# rs232module.net
KiCad netlist of a schematic drawn in EAGLE
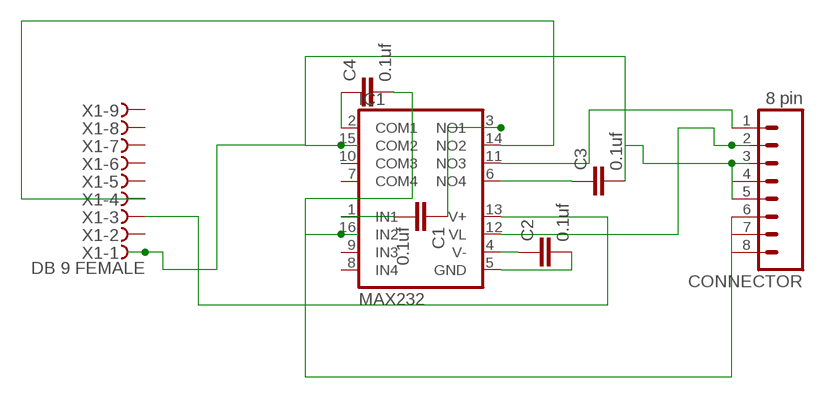
[diagram p0: schematic, sheet 1]

(export (version "E")
  (design (tool "Eeschema 10.0.6"))
  (components
    (comp (ref "C1")
      (value "0.1uf")
      (footprint "eagle-import:C2.5-3")
      (libsource (lib "eagle-import") (part "C2,5-3"))
    )
    (comp (ref "C2")
      (value "0.1uf")
      (footprint "eagle-import:C2.5-3")
      (libsource (lib "eagle-import") (part "C2,5-3"))
    )
    (comp (ref "C3")
      (value "0.1uf")
      (footprint "eagle-import:C2.5-3")
      (libsource (lib "eagle-import") (part "C2,5-3"))
    )
    (comp (ref "C4")
      (value "0.1uf")
      (footprint "eagle-import:C2.5-3")
      (libsource (lib "eagle-import") (part "C2,5-3"))
    )
    (comp (ref "CONNECTOR")
      (value "8 pin")
      (footprint "eagle-import:08P")
      (libsource (lib "eagle-import") (part "M08"))
    )
    (comp (ref "IC1")
      (value "MAX232")
      (footprint "eagle-import:DIL16")
      (fields (field (name "MPN") "MAX313EPE+"))
      (libsource (lib "eagle-import") (part "MAX313PEE"))
    )
    (comp (ref "X1")
      (value "DB 9 FEMALE")
      (footprint "eagle-import:H2M09ST")
      (libsource (lib "eagle-import") (part "D-SUB9-H2M09ST"))
    )
  )
  (nets
    (net (code "1") (name "Net-(IC1-COM1)") (class "Default")
      (node (ref "C4") (pin "1") (pinfunction "1_1") (pintype "passive"))
      (node (ref "IC1") (pin "2") (pinfunction "COM1_2") (pintype "passive"))
    )
    (net (code "2") (name "Net-(IC1-COM2)") (class "Default")
      (node (ref "C3") (pin "2") (pinfunction "2_2") (pintype "passive"))
      (node (ref "CONNECTOR") (pin "3") (pinfunction "3_3") (pintype "passive"))
      (node (ref "CONNECTOR") (pin "4") (pinfunction "4_4") (pintype "passive"))
      (node (ref "CONNECTOR") (pin "5") (pinfunction "5_5") (pintype "passive"))
      (node (ref "IC1") (pin "15") (pinfunction "COM2_15") (pintype "passive"))
      (node (ref "X1") (pin "1") (pinfunction "F_1") (pintype "passive"))
    )
    (net (code "3") (name "Net-(IC1-GND)") (class "Default")
      (node (ref "C2") (pin "2") (pinfunction "2_2") (pintype "passive"))
      (node (ref "IC1") (pin "5") (pinfunction "GND_5") (pintype "power_in"))
    )
    (net (code "4") (name "Net-(IC1-IN1)") (class "Default")
      (node (ref "C1") (pin "2") (pinfunction "2_2") (pintype "passive"))
      (node (ref "IC1") (pin "1") (pinfunction "IN1_1") (pintype "input"))
    )
    (net (code "5") (name "Net-(IC1-IN2)") (class "Default")
      (node (ref "C4") (pin "2") (pinfunction "2_2") (pintype "passive"))
      (node (ref "CONNECTOR") (pin "6") (pinfunction "6_6") (pintype "passive"))
      (node (ref "CONNECTOR") (pin "7") (pinfunction "7_7") (pintype "passive"))
      (node (ref "CONNECTOR") (pin "8") (pinfunction "8_8") (pintype "passive"))
      (node (ref "IC1") (pin "16") (pinfunction "IN2_16") (pintype "input"))
    )
    (net (code "6") (name "Net-(IC1-NO1)") (class "Default")
      (node (ref "C1") (pin "1") (pinfunction "1_1") (pintype "passive"))
      (node (ref "IC1") (pin "3") (pinfunction "NO1_3") (pintype "passive"))
    )
    (net (code "7") (name "Net-(IC1-NO2)") (class "Default")
      (node (ref "IC1") (pin "14") (pinfunction "NO2_14") (pintype "passive"))
      (node (ref "X1") (pin "4") (pinfunction "F_4") (pintype "passive"))
    )
    (net (code "8") (name "Net-(IC1-NO3)") (class "Default")
      (node (ref "CONNECTOR") (pin "1") (pinfunction "1_1") (pintype "passive"))
      (node (ref "IC1") (pin "11") (pinfunction "NO3_11") (pintype "passive"))
    )
    (net (code "9") (name "Net-(IC1-NO4)") (class "Default")
      (node (ref "C3") (pin "1") (pinfunction "1_1") (pintype "passive"))
      (node (ref "IC1") (pin "6") (pinfunction "NO4_6") (pintype "passive"))
    )
    (net (code "10") (name "Net-(IC1-V+)") (class "Default")
      (node (ref "IC1") (pin "13") (pinfunction "V+_13") (pintype "power_in"))
      (node (ref "X1") (pin "3") (pinfunction "F_3") (pintype "passive"))
    )
    (net (code "11") (name "Net-(IC1-V-)") (class "Default")
      (node (ref "C2") (pin "1") (pinfunction "1_1") (pintype "passive"))
      (node (ref "IC1") (pin "4") (pinfunction "V-_4") (pintype "power_in"))
    )
    (net (code "12") (name "Net-(IC1-VL)") (class "Default")
      (node (ref "CONNECTOR") (pin "2") (pinfunction "2_2") (pintype "passive"))
      (node (ref "IC1") (pin "12") (pinfunction "VL_12") (pintype "power_in"))
    )
    (net (code "13") (name "unconnected-(IC1-COM3-Pad10)") (class "Default")
      (node (ref "IC1") (pin "10") (pinfunction "COM3_10") (pintype "passive"))
    )
    (net (code "14") (name "unconnected-(IC1-COM4-Pad7)") (class "Default")
      (node (ref "IC1") (pin "7") (pinfunction "COM4_7") (pintype "passive"))
    )
    (net (code "15") (name "unconnected-(IC1-IN3-Pad9)") (class "Default")
      (node (ref "IC1") (pin "9") (pinfunction "IN3_9") (pintype "input"))
    )
    (net (code "16") (name "unconnected-(IC1-IN4-Pad8)") (class "Default")
      (node (ref "IC1") (pin "8") (pinfunction "IN4_8") (pintype "input"))
    )
    (net (code "17") (name "unconnected-(X1B-F-Pad2)") (class "Default")
      (node (ref "X1") (pin "2") (pinfunction "F_2") (pintype "passive"))
    )
    (net (code "18") (name "unconnected-(X1E-F-Pad5)") (class "Default")
      (node (ref "X1") (pin "5") (pinfunction "F_5") (pintype "passive"))
    )
    (net (code "19") (name "unconnected-(X1F-F-Pad6)") (class "Default")
      (node (ref "X1") (pin "6") (pinfunction "F_6") (pintype "passive"))
    )
    (net (code "20") (name "unconnected-(X1G-F-Pad7)") (class "Default")
      (node (ref "X1") (pin "7") (pinfunction "F_7") (pintype "passive"))
    )
    (net (code "21") (name "unconnected-(X1H-F-Pad8)") (class "Default")
      (node (ref "X1") (pin "8") (pinfunction "F_8") (pintype "passive"))
    )
    (net (code "22") (name "unconnected-(X1I-F-Pad9)") (class "Default")
      (node (ref "X1") (pin "9") (pinfunction "F_9") (pintype "passive"))
    )
  )
)
